# shematic.net
KiCad netlist of a schematic drawn in EAGLE
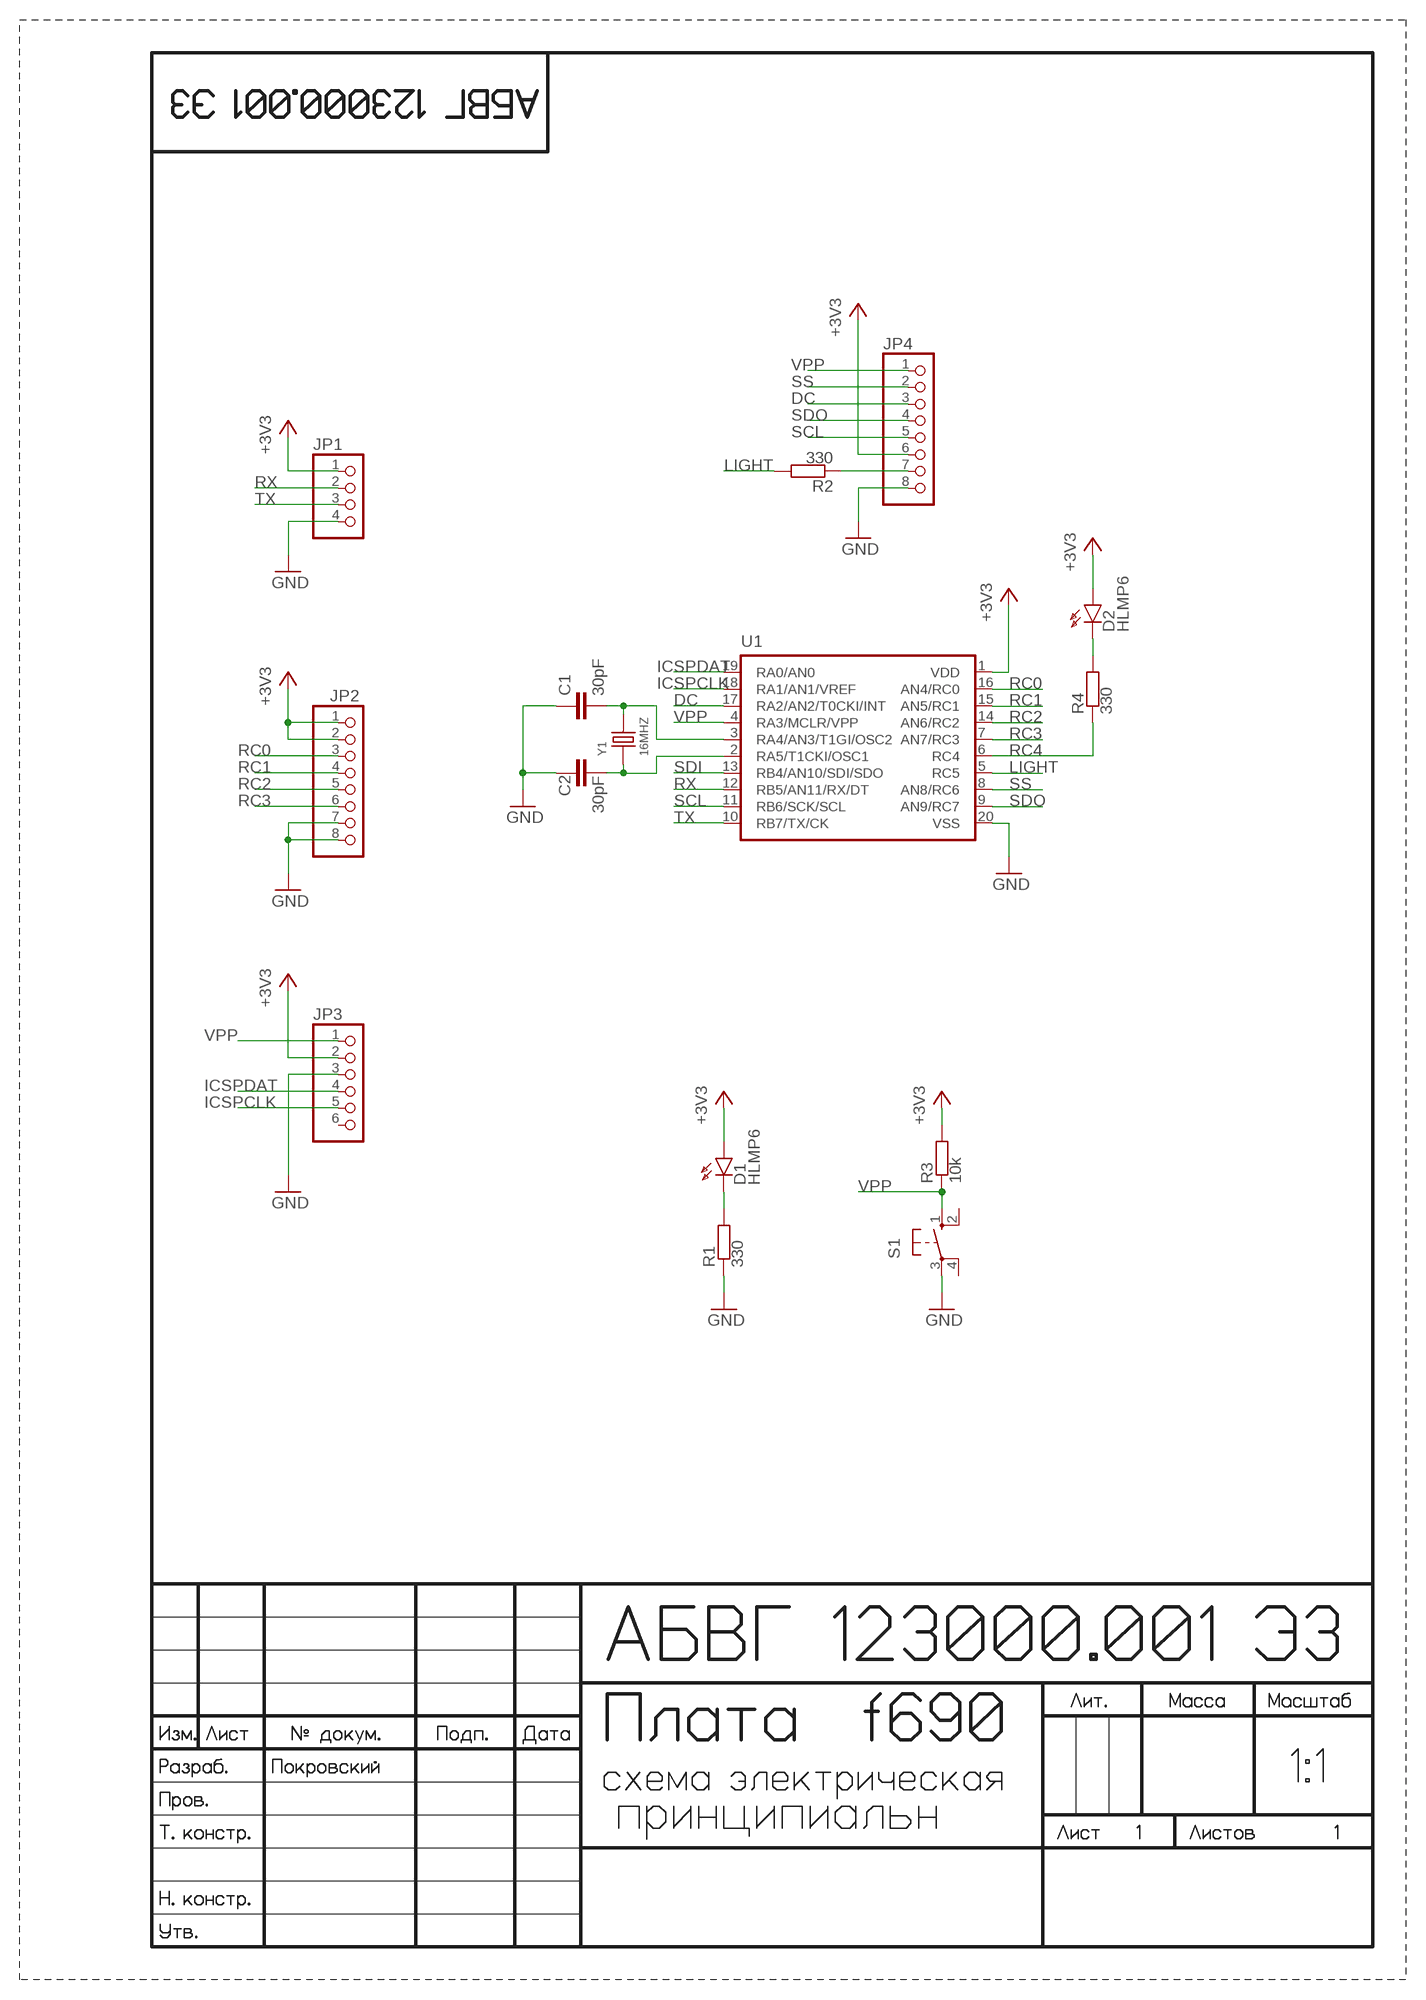
[diagram p0: schematic, sheet 1]

(export (version "E")
  (design (tool "Eeschema 10.0.6"))
  (components
    (comp (ref "C1")
      (value "30pF")
      (footprint "eagle-import:C5B2.5")
      (libsource (lib "eagle-import") (part "C5/2.5"))
    )
    (comp (ref "C2")
      (value "30pF")
      (footprint "eagle-import:C5B2.5")
      (libsource (lib "eagle-import") (part "C5/2.5"))
    )
    (comp (ref "D1")
      (value "HLMP6")
      (footprint "eagle-import:HLMP6")
      (fields (field (name "MF") "AGILENT TECHNOLOGIES") (field (name "MPN") "HLMP-6500"))
      (libsource (lib "eagle-import") (part "HLMP6"))
    )
    (comp (ref "D2")
      (value "HLMP6")
      (footprint "eagle-import:HLMP6")
      (fields (field (name "MF") "AGILENT TECHNOLOGIES") (field (name "MPN") "HLMP-6500"))
      (libsource (lib "eagle-import") (part "HLMP6"))
    )
    (comp (ref "JP1")
      (value "PINHD-1X4/90")
      (footprint "eagle-import:1X04_90")
      (libsource (lib "eagle-import") (part "PINHD-1X4/90"))
    )
    (comp (ref "JP2")
      (value "PINHD-1X8")
      (footprint "eagle-import:1X08")
      (libsource (lib "eagle-import") (part "PINHD-1X8"))
    )
    (comp (ref "JP3")
      (value "PINHD-1X6/90")
      (footprint "eagle-import:1X06_90")
      (libsource (lib "eagle-import") (part "PINHD-1X6/90"))
    )
    (comp (ref "JP4")
      (value "PINHD-1X8")
      (footprint "eagle-import:1X08")
      (libsource (lib "eagle-import") (part "PINHD-1X8"))
    )
    (comp (ref "R1")
      (value "330")
      (footprint "eagle-import:R0805")
      (libsource (lib "eagle-import") (part "R-EU_R0805"))
    )
    (comp (ref "R2")
      (value "330")
      (footprint "eagle-import:R0805")
      (libsource (lib "eagle-import") (part "R-EU_R0805"))
    )
    (comp (ref "R3")
      (value "10k")
      (footprint "eagle-import:0204_7")
      (libsource (lib "eagle-import") (part "R-EU_0204/7"))
    )
    (comp (ref "R4")
      (value "330")
      (footprint "eagle-import:R0805")
      (libsource (lib "eagle-import") (part "R-EU_R0805"))
    )
    (comp (ref "S1")
      (value "10-XX")
      (footprint "eagle-import:B3F-10XX")
      (fields (field (name "MPN") "B3F-1000"))
      (libsource (lib "eagle-import") (part "10-XX"))
    )
    (comp (ref "U1")
      (value "PIC16F6XX")
      (footprint "eagle-import:DIL20")
      (libsource (lib "eagle-import") (part "PIC16F6XX"))
    )
    (comp (ref "Y1")
      (value "16MHZ")
      (footprint "eagle-import:HC49US")
      (fields (field (name "MPN") "HC-49US    16.000MHz"))
      (libsource (lib "eagle-import") (part "DIP-CRYSTAL-16MHZ-18PF-30PPM-40R(HC49US)"))
    )
  )
  (nets
    (net (code "1") (name "+3V3") (class "Default")
      (node (ref "D1") (pin "A") (pinfunction "A_A") (pintype "passive"))
      (node (ref "D2") (pin "A") (pinfunction "A_A") (pintype "passive"))
      (node (ref "JP1") (pin "1") (pinfunction "1_1") (pintype "passive"))
      (node (ref "JP2") (pin "1") (pinfunction "1_1") (pintype "passive"))
      (node (ref "JP2") (pin "2") (pinfunction "2_2") (pintype "passive"))
      (node (ref "JP3") (pin "2") (pinfunction "2_2") (pintype "passive"))
      (node (ref "JP4") (pin "6") (pinfunction "6_6") (pintype "passive"))
      (node (ref "R3") (pin "2") (pinfunction "2_2") (pintype "passive"))
      (node (ref "U1") (pin "1") (pinfunction "VDD_1") (pintype "power_in"))
    )
    (net (code "2") (name "/DC") (class "Default")
      (node (ref "JP4") (pin "3") (pinfunction "3_3") (pintype "passive"))
      (node (ref "U1") (pin "17") (pinfunction "RA2/AN2/T0CKI/INT_17") (pintype "bidirectional"))
    )
    (net (code "3") (name "/ICSPCLK") (class "Default")
      (node (ref "JP3") (pin "5") (pinfunction "5_5") (pintype "passive"))
      (node (ref "U1") (pin "18") (pinfunction "RA1/AN1/VREF_18") (pintype "bidirectional"))
    )
    (net (code "4") (name "/ICSPDAT") (class "Default")
      (node (ref "JP3") (pin "4") (pinfunction "4_4") (pintype "passive"))
      (node (ref "U1") (pin "19") (pinfunction "RA0/AN0_19") (pintype "bidirectional"))
    )
    (net (code "5") (name "/LIGHT") (class "Default")
      (node (ref "R2") (pin "2") (pinfunction "2_2") (pintype "passive"))
      (node (ref "U1") (pin "5") (pinfunction "RC5_5") (pintype "bidirectional"))
    )
    (net (code "6") (name "/RC0") (class "Default")
      (node (ref "JP2") (pin "3") (pinfunction "3_3") (pintype "passive"))
      (node (ref "U1") (pin "16") (pinfunction "AN4/RC0_16") (pintype "bidirectional"))
    )
    (net (code "7") (name "/RC1") (class "Default")
      (node (ref "JP2") (pin "4") (pinfunction "4_4") (pintype "passive"))
      (node (ref "U1") (pin "15") (pinfunction "AN5/RC1_15") (pintype "bidirectional"))
    )
    (net (code "8") (name "/RC2") (class "Default")
      (node (ref "JP2") (pin "5") (pinfunction "5_5") (pintype "passive"))
      (node (ref "U1") (pin "14") (pinfunction "AN6/RC2_14") (pintype "bidirectional"))
    )
    (net (code "9") (name "/RC3") (class "Default")
      (node (ref "JP2") (pin "6") (pinfunction "6_6") (pintype "passive"))
      (node (ref "U1") (pin "7") (pinfunction "AN7/RC3_7") (pintype "bidirectional"))
    )
    (net (code "10") (name "/RC4") (class "Default")
      (node (ref "R4") (pin "1") (pinfunction "1_1") (pintype "passive"))
      (node (ref "U1") (pin "6") (pinfunction "RC4_6") (pintype "bidirectional"))
    )
    (net (code "11") (name "/RX") (class "Default")
      (node (ref "JP1") (pin "2") (pinfunction "2_2") (pintype "passive"))
      (node (ref "U1") (pin "12") (pinfunction "RB5/AN11/RX/DT_12") (pintype "bidirectional"))
    )
    (net (code "12") (name "/SCL") (class "Default")
      (node (ref "JP4") (pin "5") (pinfunction "5_5") (pintype "passive"))
      (node (ref "U1") (pin "11") (pinfunction "RB6/SCK/SCL_11") (pintype "bidirectional"))
    )
    (net (code "13") (name "/SDI") (class "Default")
      (node (ref "U1") (pin "13") (pinfunction "RB4/AN10/SDI/SDO_13") (pintype "bidirectional"))
    )
    (net (code "14") (name "/SDO") (class "Default")
      (node (ref "JP4") (pin "4") (pinfunction "4_4") (pintype "passive"))
      (node (ref "U1") (pin "9") (pinfunction "AN9/RC7_9") (pintype "bidirectional"))
    )
    (net (code "15") (name "/SS") (class "Default")
      (node (ref "JP4") (pin "2") (pinfunction "2_2") (pintype "passive"))
      (node (ref "U1") (pin "8") (pinfunction "AN8/RC6_8") (pintype "bidirectional"))
    )
    (net (code "16") (name "/TX") (class "Default")
      (node (ref "JP1") (pin "3") (pinfunction "3_3") (pintype "passive"))
      (node (ref "U1") (pin "10") (pinfunction "RB7/TX/CK_10") (pintype "bidirectional"))
    )
    (net (code "17") (name "/VPP") (class "Default")
      (node (ref "JP3") (pin "1") (pinfunction "1_1") (pintype "passive"))
      (node (ref "JP4") (pin "1") (pinfunction "1_1") (pintype "passive"))
      (node (ref "R3") (pin "1") (pinfunction "1_1") (pintype "passive"))
      (node (ref "S1") (pin "1") (pinfunction "S_1") (pintype "passive"))
      (node (ref "U1") (pin "4") (pinfunction "RA3/MCLR/VPP_4") (pintype "input"))
    )
    (net (code "18") (name "GND") (class "Default")
      (node (ref "C1") (pin "1") (pinfunction "1_1") (pintype "passive"))
      (node (ref "C2") (pin "1") (pinfunction "1_1") (pintype "passive"))
      (node (ref "JP1") (pin "4") (pinfunction "4_4") (pintype "passive"))
      (node (ref "JP2") (pin "7") (pinfunction "7_7") (pintype "passive"))
      (node (ref "JP2") (pin "8") (pinfunction "8_8") (pintype "passive"))
      (node (ref "JP3") (pin "3") (pinfunction "3_3") (pintype "passive"))
      (node (ref "JP4") (pin "8") (pinfunction "8_8") (pintype "passive"))
      (node (ref "R1") (pin "1") (pinfunction "1_1") (pintype "passive"))
      (node (ref "S1") (pin "3") (pinfunction "P_3") (pintype "passive"))
      (node (ref "U1") (pin "20") (pinfunction "VSS_20") (pintype "power_in"))
    )
    (net (code "19") (name "Net-(D1-PadK)") (class "Default")
      (node (ref "D1") (pin "K") (pinfunction "K_K") (pintype "passive"))
      (node (ref "R1") (pin "2") (pinfunction "2_2") (pintype "passive"))
    )
    (net (code "20") (name "Net-(D2-PadK)") (class "Default")
      (node (ref "D2") (pin "K") (pinfunction "K_K") (pintype "passive"))
      (node (ref "R4") (pin "2") (pinfunction "2_2") (pintype "passive"))
    )
    (net (code "21") (name "Net-(JP4-Pad7)") (class "Default")
      (node (ref "JP4") (pin "7") (pinfunction "7_7") (pintype "passive"))
      (node (ref "R2") (pin "1") (pinfunction "1_1") (pintype "passive"))
    )
    (net (code "22") (name "Net-(U1-RA4{slash}AN3{slash}T1GI{slash}OSC2)") (class "Default")
      (node (ref "C1") (pin "2") (pinfunction "2_2") (pintype "passive"))
      (node (ref "U1") (pin "3") (pinfunction "RA4/AN3/T1GI/OSC2_3") (pintype "bidirectional"))
      (node (ref "Y1") (pin "2") (pinfunction "2_2") (pintype "passive"))
    )
    (net (code "23") (name "Net-(U1-RA5{slash}T1CKI{slash}OSC1)") (class "Default")
      (node (ref "C2") (pin "2") (pinfunction "2_2") (pintype "passive"))
      (node (ref "U1") (pin "2") (pinfunction "RA5/T1CKI/OSC1_2") (pintype "bidirectional"))
      (node (ref "Y1") (pin "1") (pinfunction "1_1") (pintype "passive"))
    )
    (net (code "24") (name "unconnected-(JP3-Pad6)") (class "Default")
      (node (ref "JP3") (pin "6") (pinfunction "6_6") (pintype "passive"))
    )
    (net (code "25") (name "unconnected-(S1-P1-Pad4)") (class "Default")
      (node (ref "S1") (pin "4") (pinfunction "P1_4") (pintype "passive"))
    )
    (net (code "26") (name "unconnected-(S1-S1-Pad2)") (class "Default")
      (node (ref "S1") (pin "2") (pinfunction "S1_2") (pintype "passive"))
    )
  )
)
